# qcopter_joystick.net
KiCad netlist of a schematic drawn in EAGLE
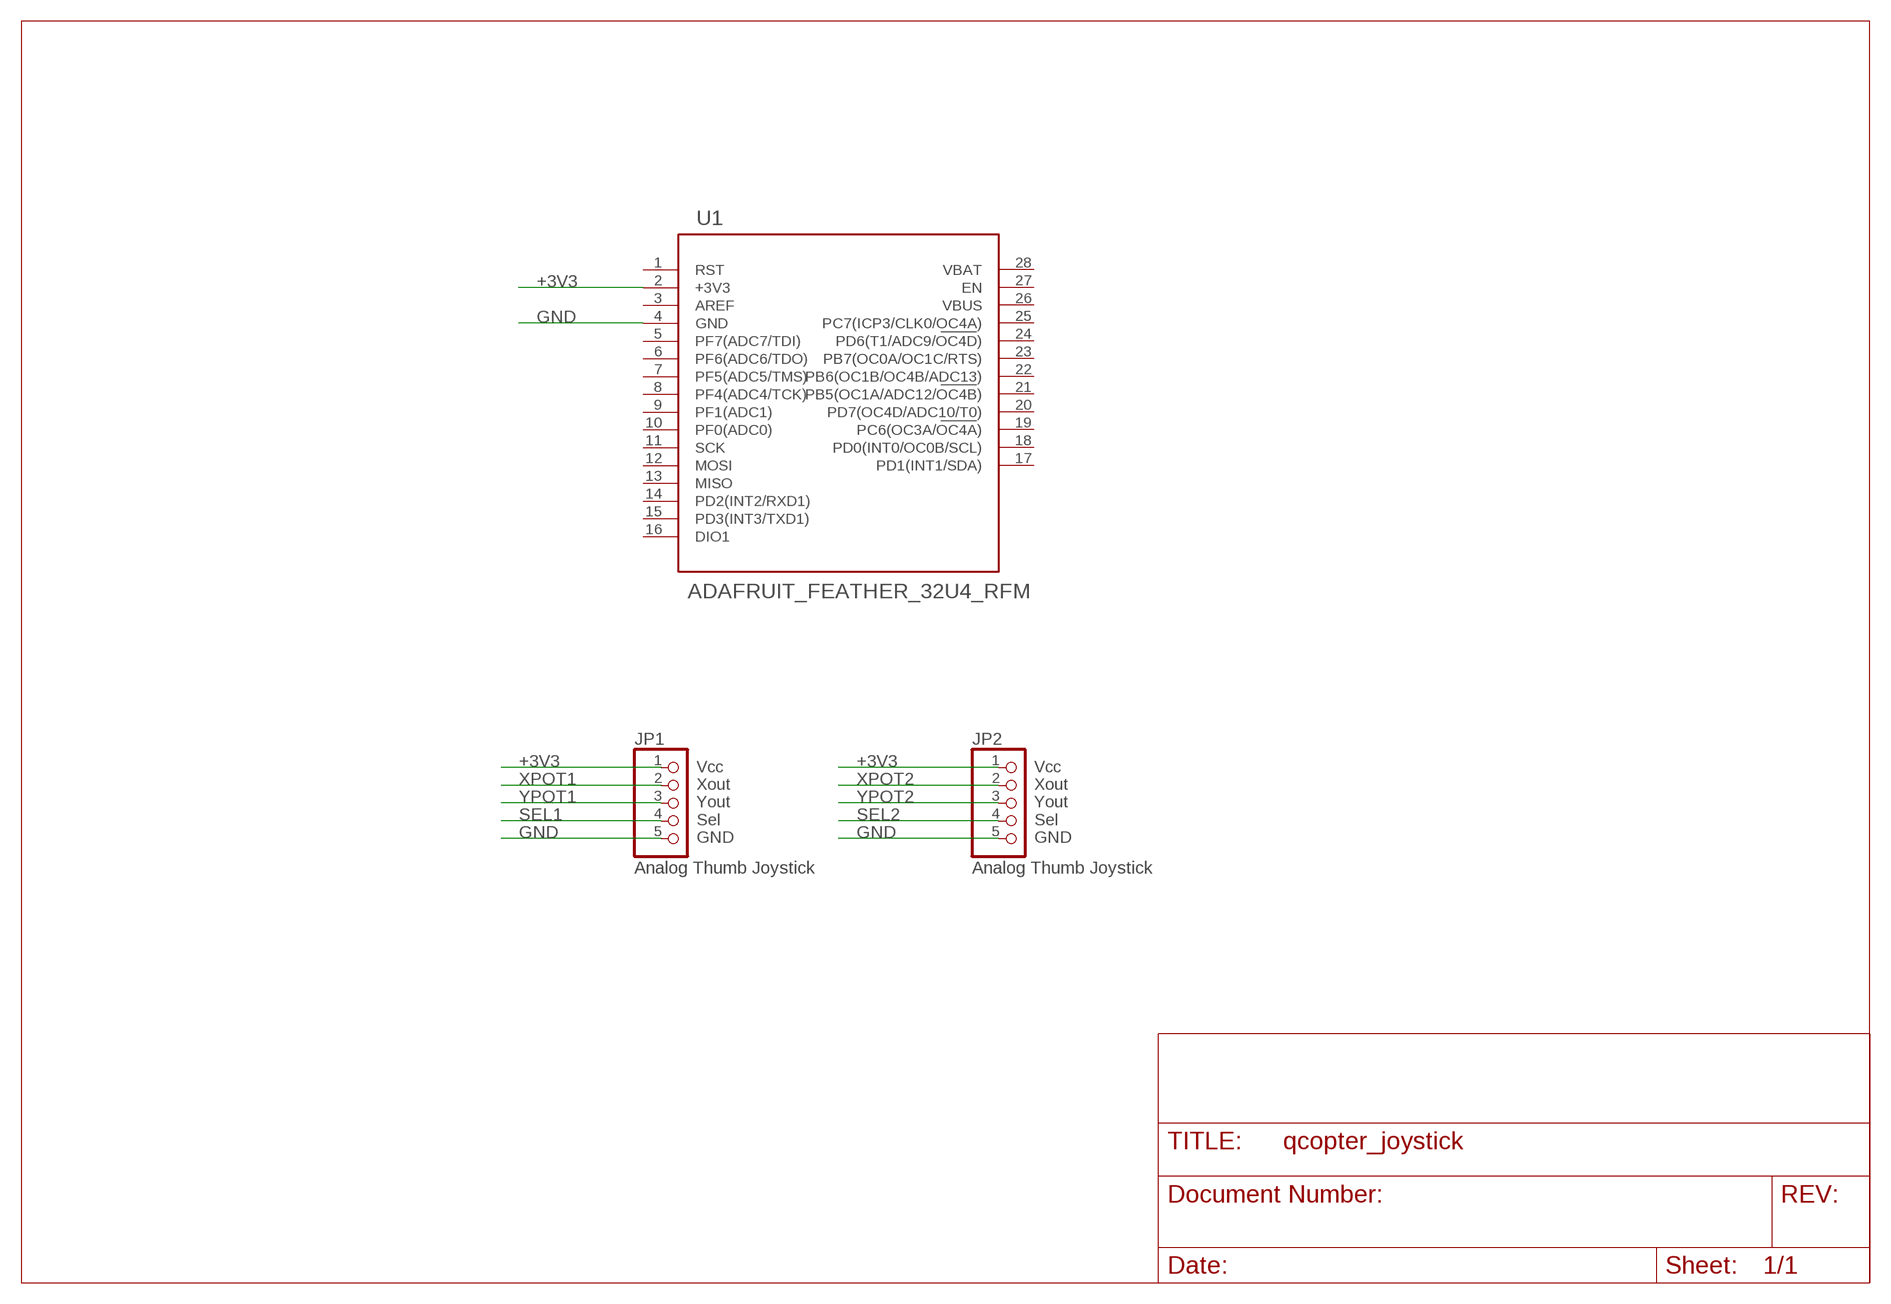
[diagram p0: schematic, sheet 1]

(export (version "E")
  (design (tool "Eeschema 10.0.6"))
  (components
    (comp (ref "JP1")
      (value "Analog Thumb Joystick")
      (footprint "eagle-import:1X05")
      (libsource (lib "eagle-import") (part "PINHD-1X5"))
    )
    (comp (ref "JP2")
      (value "Analog Thumb Joystick")
      (footprint "eagle-import:1X05")
      (libsource (lib "eagle-import") (part "PINHD-1X5"))
    )
    (comp (ref "U1")
      (value "ADAFRUIT_FEATHER_32U4_RFM")
      (footprint "eagle-import:ADAFRUIT_FEATHER_32U4_RFM")
      (libsource (lib "eagle-import") (part "ADAFRUIT_FEATHER_32U4_RFM"))
    )
  )
  (nets
    (net (code "1") (name "/+3V3") (class "Default")
      (node (ref "JP1") (pin "1") (pinfunction "1_1") (pintype "passive"))
      (node (ref "JP2") (pin "1") (pinfunction "1_1") (pintype "passive"))
      (node (ref "U1") (pin "2") (pinfunction "+3V3_2") (pintype "bidirectional"))
    )
    (net (code "2") (name "/GND") (class "Default")
      (node (ref "JP1") (pin "5") (pinfunction "5_5") (pintype "passive"))
      (node (ref "JP2") (pin "5") (pinfunction "5_5") (pintype "passive"))
      (node (ref "U1") (pin "4") (pinfunction "GND_4") (pintype "bidirectional"))
    )
    (net (code "3") (name "/SEL1") (class "Default")
      (node (ref "JP1") (pin "4") (pinfunction "4_4") (pintype "passive"))
    )
    (net (code "4") (name "/SEL2") (class "Default")
      (node (ref "JP2") (pin "4") (pinfunction "4_4") (pintype "passive"))
    )
    (net (code "5") (name "/XPOT1") (class "Default")
      (node (ref "JP1") (pin "2") (pinfunction "2_2") (pintype "passive"))
    )
    (net (code "6") (name "/XPOT2") (class "Default")
      (node (ref "JP2") (pin "2") (pinfunction "2_2") (pintype "passive"))
    )
    (net (code "7") (name "/YPOT1") (class "Default")
      (node (ref "JP1") (pin "3") (pinfunction "3_3") (pintype "passive"))
    )
    (net (code "8") (name "/YPOT2") (class "Default")
      (node (ref "JP2") (pin "3") (pinfunction "3_3") (pintype "passive"))
    )
    (net (code "9") (name "unconnected-(U1-AREF-Pad3)") (class "Default")
      (node (ref "U1") (pin "3") (pinfunction "AREF_3") (pintype "bidirectional"))
    )
    (net (code "10") (name "unconnected-(U1-DIO1-Pad16)") (class "Default")
      (node (ref "U1") (pin "16") (pinfunction "DIO1_16") (pintype "bidirectional"))
    )
    (net (code "11") (name "unconnected-(U1-EN-Pad27)") (class "Default")
      (node (ref "U1") (pin "27") (pinfunction "EN_27") (pintype "bidirectional"))
    )
    (net (code "12") (name "unconnected-(U1-MISO-Pad13)") (class "Default")
      (node (ref "U1") (pin "13") (pinfunction "MISO_13") (pintype "bidirectional"))
    )
    (net (code "13") (name "unconnected-(U1-MOSI-Pad12)") (class "Default")
      (node (ref "U1") (pin "12") (pinfunction "MOSI_12") (pintype "bidirectional"))
    )
    (net (code "14") (name "unconnected-(U1-PB5(OC1A{slash}ADC12{slash}OC4B)-Pad21)") (class "Default")
      (node (ref "U1") (pin "21") (pinfunction "PB5(OC1A/ADC12/OC4B)_21") (pintype "bidirectional"))
    )
    (net (code "15") (name "unconnected-(U1-PB6(OC1B{slash}OC4B{slash}ADC13)-Pad22)") (class "Default")
      (node (ref "U1") (pin "22") (pinfunction "PB6(OC1B/OC4B/ADC13)_22") (pintype "bidirectional"))
    )
    (net (code "16") (name "unconnected-(U1-PB7(OC0A{slash}OC1C{slash}RTS)-Pad23)") (class "Default")
      (node (ref "U1") (pin "23") (pinfunction "PB7(OC0A/OC1C/RTS)_23") (pintype "bidirectional"))
    )
    (net (code "17") (name "unconnected-(U1-PC6(OC3A{slash}OC4A)-Pad19)") (class "Default")
      (node (ref "U1") (pin "19") (pinfunction "PC6(OC3A/OC4A)_19") (pintype "bidirectional"))
    )
    (net (code "18") (name "unconnected-(U1-PC7(ICP3{slash}CLK0{slash}OC4A)-Pad25)") (class "Default")
      (node (ref "U1") (pin "25") (pinfunction "PC7(ICP3/CLK0/OC4A)_25") (pintype "bidirectional"))
    )
    (net (code "19") (name "unconnected-(U1-PD0(INT0{slash}OC0B{slash}SCL)-Pad18)") (class "Default")
      (node (ref "U1") (pin "18") (pinfunction "PD0(INT0/OC0B/SCL)_18") (pintype "bidirectional"))
    )
    (net (code "20") (name "unconnected-(U1-PD1(INT1{slash}SDA)-Pad17)") (class "Default")
      (node (ref "U1") (pin "17") (pinfunction "PD1(INT1/SDA)_17") (pintype "bidirectional"))
    )
    (net (code "21") (name "unconnected-(U1-PD2(INT2{slash}RXD1)-Pad14)") (class "Default")
      (node (ref "U1") (pin "14") (pinfunction "PD2(INT2/RXD1)_14") (pintype "bidirectional"))
    )
    (net (code "22") (name "unconnected-(U1-PD3(INT3{slash}TXD1)-Pad15)") (class "Default")
      (node (ref "U1") (pin "15") (pinfunction "PD3(INT3/TXD1)_15") (pintype "bidirectional"))
    )
    (net (code "23") (name "unconnected-(U1-PD6(T1{slash}ADC9{slash}OC4D)-Pad24)") (class "Default")
      (node (ref "U1") (pin "24") (pinfunction "PD6(T1/ADC9/OC4D)_24") (pintype "bidirectional"))
    )
    (net (code "24") (name "unconnected-(U1-PD7(OC4D{slash}ADC10{slash}T0)-Pad20)") (class "Default")
      (node (ref "U1") (pin "20") (pinfunction "PD7(OC4D/ADC10/T0)_20") (pintype "bidirectional"))
    )
    (net (code "25") (name "unconnected-(U1-PF0(ADC0)-Pad10)") (class "Default")
      (node (ref "U1") (pin "10") (pinfunction "PF0(ADC0)_10") (pintype "bidirectional"))
    )
    (net (code "26") (name "unconnected-(U1-PF1(ADC1)-Pad9)") (class "Default")
      (node (ref "U1") (pin "9") (pinfunction "PF1(ADC1)_9") (pintype "bidirectional"))
    )
    (net (code "27") (name "unconnected-(U1-PF4(ADC4{slash}TCK)-Pad8)") (class "Default")
      (node (ref "U1") (pin "8") (pinfunction "PF4(ADC4/TCK)_8") (pintype "bidirectional"))
    )
    (net (code "28") (name "unconnected-(U1-PF5(ADC5{slash}TMS)-Pad7)") (class "Default")
      (node (ref "U1") (pin "7") (pinfunction "PF5(ADC5/TMS)_7") (pintype "bidirectional"))
    )
    (net (code "29") (name "unconnected-(U1-PF6(ADC6{slash}TDO)-Pad6)") (class "Default")
      (node (ref "U1") (pin "6") (pinfunction "PF6(ADC6/TDO)_6") (pintype "bidirectional"))
    )
    (net (code "30") (name "unconnected-(U1-PF7(ADC7{slash}TDI)-Pad5)") (class "Default")
      (node (ref "U1") (pin "5") (pinfunction "PF7(ADC7/TDI)_5") (pintype "bidirectional"))
    )
    (net (code "31") (name "unconnected-(U1-RST-Pad1)") (class "Default")
      (node (ref "U1") (pin "1") (pinfunction "RST_1") (pintype "bidirectional"))
    )
    (net (code "32") (name "unconnected-(U1-SCK-Pad11)") (class "Default")
      (node (ref "U1") (pin "11") (pinfunction "SCK_11") (pintype "bidirectional"))
    )
    (net (code "33") (name "unconnected-(U1-VBAT-Pad28)") (class "Default")
      (node (ref "U1") (pin "28") (pinfunction "VBAT_28") (pintype "bidirectional"))
    )
    (net (code "34") (name "unconnected-(U1-VBUS-Pad26)") (class "Default")
      (node (ref "U1") (pin "26") (pinfunction "VBUS_26") (pintype "bidirectional"))
    )
  )
)
